# INCUBATOR.net
KiCad netlist of a schematic drawn in EAGLE
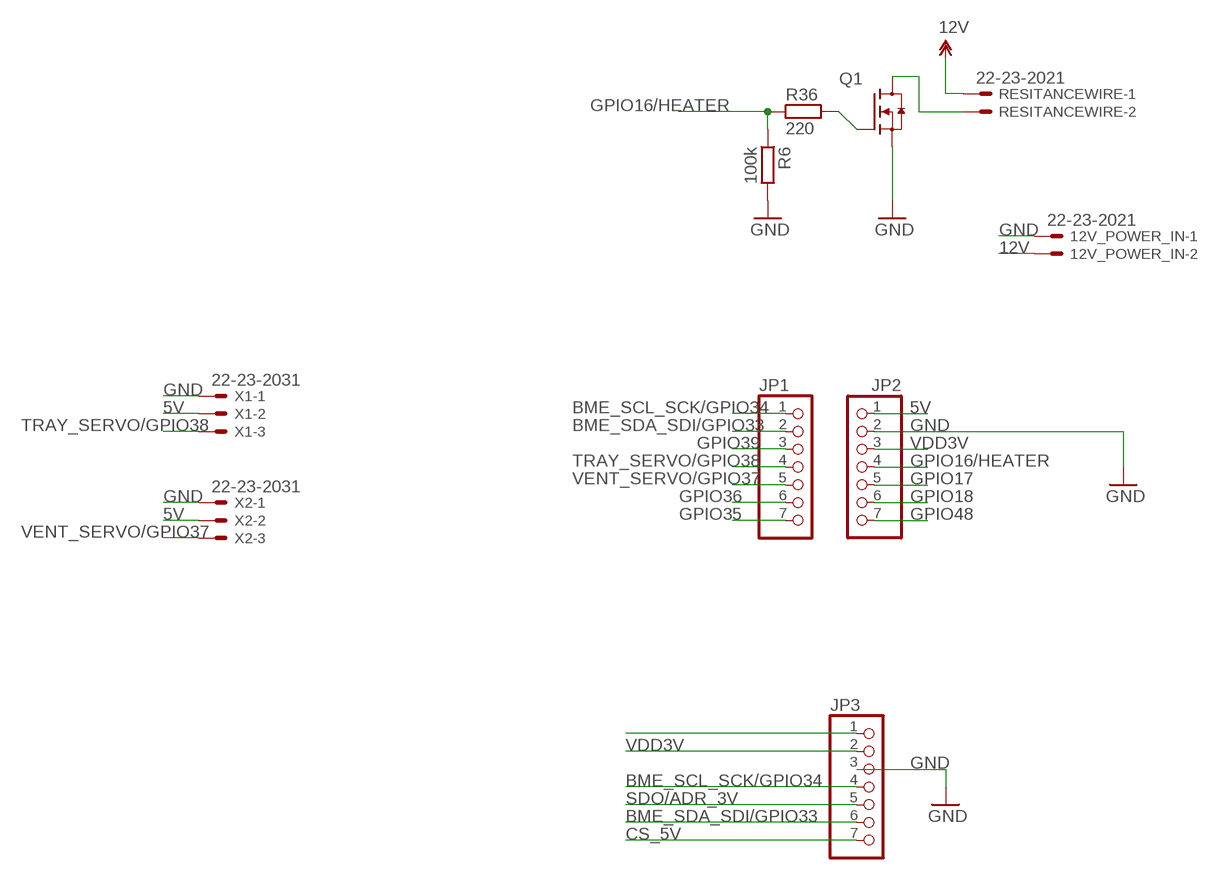
[diagram p0: schematic, sheet 1]

(export (version "E")
  (design (tool "Eeschema 10.0.6"))
  (components
    (comp (ref "12V_POWER_IN")
      (value "22-23-2021")
      (footprint "eagle-import:22-23-2021")
      (fields (field (name "MF") "MOLEX"))
      (libsource (lib "eagle-import") (part "22-23-2021"))
    )
    (comp (ref "JP1")
      (value "PINHD-1X7")
      (footprint "eagle-import:1X07")
      (libsource (lib "eagle-import") (part "PINHD-1X7"))
    )
    (comp (ref "JP2")
      (value "PINHD-1X7")
      (footprint "eagle-import:1X07")
      (libsource (lib "eagle-import") (part "PINHD-1X7"))
    )
    (comp (ref "JP3")
      (value "HEADER-1X770MIL")
      (footprint "eagle-import:1X07_ROUND_70")
      (libsource (lib "eagle-import") (part "HEADER-1X770MIL"))
    )
    (comp (ref "Q1")
      (value "RFP30N06LE")
      (footprint "eagle-import:TO92127P520H700-3")
      (libsource (lib "eagle-import") (part "TN0702N3-G"))
    )
    (comp (ref "R6")
      (value "100k")
      (footprint "eagle-import:RESC2012X70N")
      (libsource (lib "eagle-import") (part "RESISTOR_0805"))
    )
    (comp (ref "R36")
      (value "220")
      (footprint "eagle-import:RESC2012X70N")
      (libsource (lib "eagle-import") (part "RESISTOR_0805"))
    )
    (comp (ref "RESITANCEWIRE")
      (value "22-23-2021")
      (footprint "eagle-import:22-23-2021")
      (fields (field (name "MF") "MOLEX"))
      (libsource (lib "eagle-import") (part "22-23-2021"))
    )
    (comp (ref "X1")
      (value "22-23-2031")
      (footprint "eagle-import:22-23-2031")
      (fields (field (name "MF") "MOLEX"))
      (libsource (lib "eagle-import") (part "22-23-2031"))
    )
    (comp (ref "X2")
      (value "22-23-2031")
      (footprint "eagle-import:22-23-2031")
      (fields (field (name "MF") "MOLEX"))
      (libsource (lib "eagle-import") (part "22-23-2031"))
    )
  )
  (nets
    (net (code "1") (name "/5V") (class "Default")
      (node (ref "JP2") (pin "1") (pinfunction "1_1") (pintype "passive"))
      (node (ref "X1") (pin "2") (pinfunction "S_2") (pintype "passive"))
      (node (ref "X2") (pin "2") (pinfunction "S_2") (pintype "passive"))
    )
    (net (code "2") (name "/BME_SCL_SCK{slash}GPIO34") (class "Default")
      (node (ref "JP1") (pin "1") (pinfunction "1_1") (pintype "passive"))
      (node (ref "JP3") (pin "4") (pinfunction "4_4") (pintype "passive"))
    )
    (net (code "3") (name "/BME_SDA_SDI{slash}GPIO33") (class "Default")
      (node (ref "JP1") (pin "2") (pinfunction "2_2") (pintype "passive"))
      (node (ref "JP3") (pin "6") (pinfunction "6_6") (pintype "passive"))
    )
    (net (code "4") (name "/CS_5V") (class "Default")
      (node (ref "JP3") (pin "7") (pinfunction "7_7") (pintype "passive"))
    )
    (net (code "5") (name "/GPIO16{slash}HEATER") (class "Default")
      (node (ref "JP2") (pin "4") (pinfunction "4_4") (pintype "passive"))
      (node (ref "R36") (pin "1") (pinfunction "1_1") (pintype "passive"))
      (node (ref "R6") (pin "1") (pinfunction "1_1") (pintype "passive"))
    )
    (net (code "6") (name "/GPIO17") (class "Default")
      (node (ref "JP2") (pin "5") (pinfunction "5_5") (pintype "passive"))
    )
    (net (code "7") (name "/GPIO18") (class "Default")
      (node (ref "JP2") (pin "6") (pinfunction "6_6") (pintype "passive"))
    )
    (net (code "8") (name "/GPIO35") (class "Default")
      (node (ref "JP1") (pin "7") (pinfunction "7_7") (pintype "passive"))
    )
    (net (code "9") (name "/GPIO36") (class "Default")
      (node (ref "JP1") (pin "6") (pinfunction "6_6") (pintype "passive"))
    )
    (net (code "10") (name "/GPIO39") (class "Default")
      (node (ref "JP1") (pin "3") (pinfunction "3_3") (pintype "passive"))
    )
    (net (code "11") (name "/GPIO48") (class "Default")
      (node (ref "JP2") (pin "7") (pinfunction "7_7") (pintype "passive"))
    )
    (net (code "12") (name "/SDO{slash}ADR_3V") (class "Default")
      (node (ref "JP3") (pin "5") (pinfunction "5_5") (pintype "passive"))
    )
    (net (code "13") (name "/TRAY_SERVO{slash}GPIO38") (class "Default")
      (node (ref "JP1") (pin "4") (pinfunction "4_4") (pintype "passive"))
      (node (ref "X1") (pin "3") (pinfunction "S_3") (pintype "passive"))
    )
    (net (code "14") (name "/VDD3V") (class "Default")
      (node (ref "JP2") (pin "3") (pinfunction "3_3") (pintype "passive"))
      (node (ref "JP3") (pin "2") (pinfunction "2_2") (pintype "passive"))
    )
    (net (code "15") (name "/VENT_SERVO{slash}GPIO37") (class "Default")
      (node (ref "JP1") (pin "5") (pinfunction "5_5") (pintype "passive"))
      (node (ref "X2") (pin "3") (pinfunction "S_3") (pintype "passive"))
    )
    (net (code "16") (name "12V") (class "Default")
      (node (ref "12V_POWER_IN") (pin "2") (pinfunction "S_2") (pintype "passive"))
      (node (ref "RESITANCEWIRE") (pin "1") (pinfunction "S_1") (pintype "passive"))
    )
    (net (code "17") (name "GND") (class "Default")
      (node (ref "12V_POWER_IN") (pin "1") (pinfunction "S_1") (pintype "passive"))
      (node (ref "JP2") (pin "2") (pinfunction "2_2") (pintype "passive"))
      (node (ref "JP3") (pin "3") (pinfunction "3_3") (pintype "passive"))
      (node (ref "Q1") (pin "S") (pinfunction "SOURCE_S") (pintype "passive"))
      (node (ref "R6") (pin "2") (pinfunction "2_2") (pintype "passive"))
      (node (ref "X1") (pin "1") (pinfunction "S_1") (pintype "passive"))
      (node (ref "X2") (pin "1") (pinfunction "S_1") (pintype "passive"))
    )
    (net (code "18") (name "Net-(Q1-DRAIN)") (class "Default")
      (node (ref "Q1") (pin "D") (pinfunction "DRAIN_D") (pintype "passive"))
      (node (ref "RESITANCEWIRE") (pin "2") (pinfunction "S_2") (pintype "passive"))
    )
    (net (code "19") (name "Net-(Q1-GATE)") (class "Default")
      (node (ref "Q1") (pin "G") (pinfunction "GATE_G") (pintype "passive"))
      (node (ref "R36") (pin "2") (pinfunction "2_2") (pintype "passive"))
    )
    (net (code "20") (name "unconnected-(JP3-Pad1)") (class "Default")
      (node (ref "JP3") (pin "1") (pinfunction "1_1") (pintype "passive"))
    )
  )
)
